# STM32G473CET6_PINOUT.net
KiCad netlist of a schematic drawn in Altium Designer
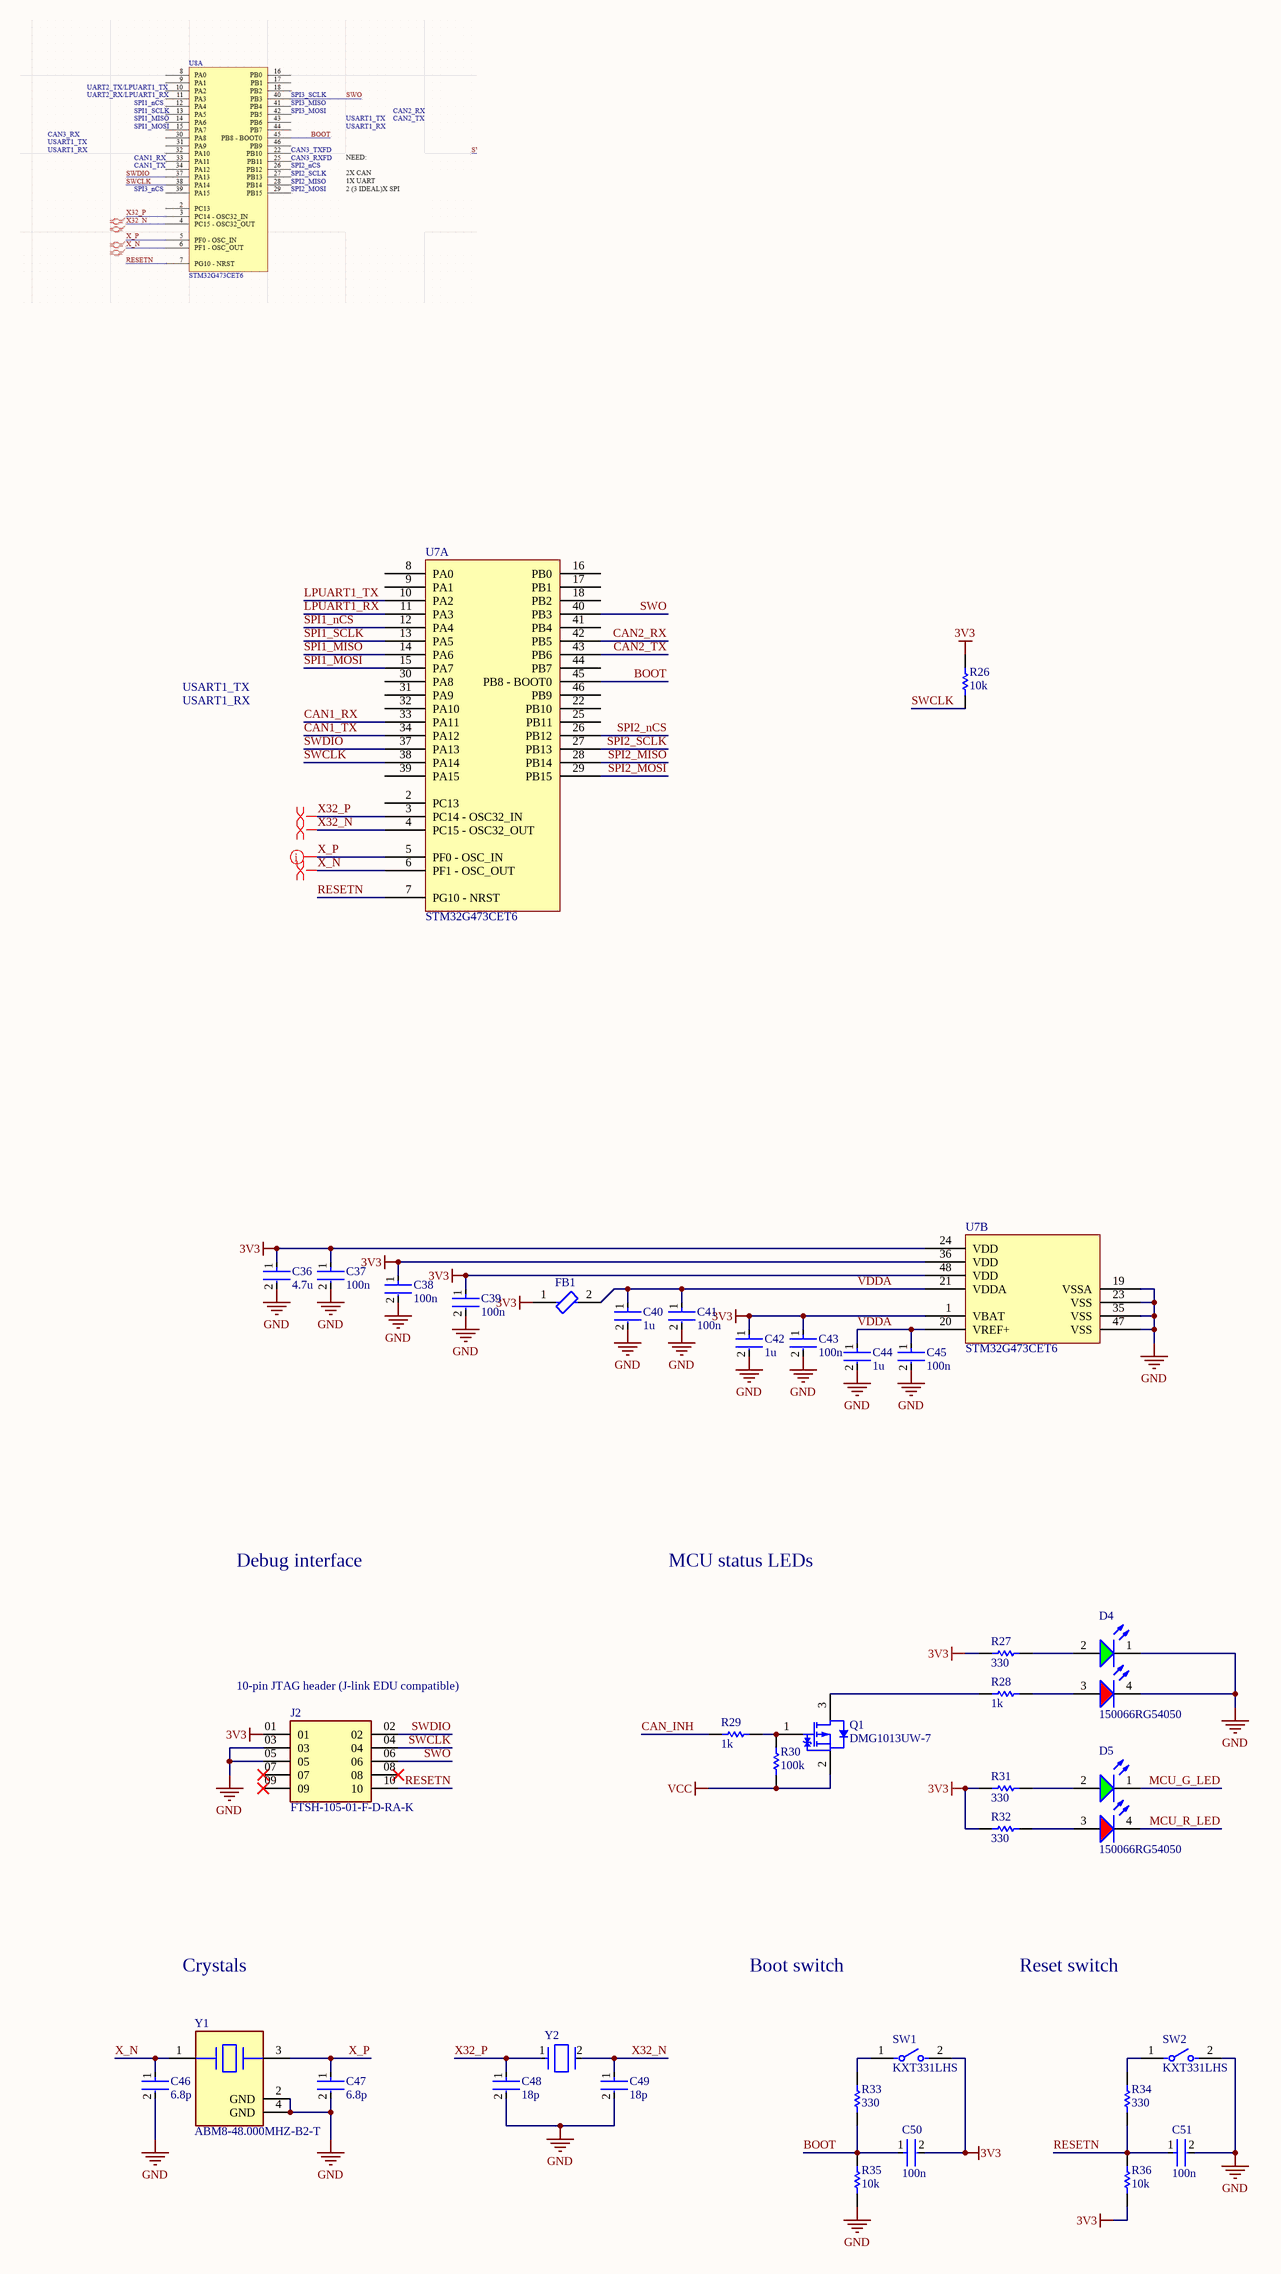
[diagram p0: STM32G473CET6_PINOUT.SchDoc]

(export (version "E")
  (design (tool "Eeschema 10.0.6"))
  (components
    (comp (ref "C36")
      (value "4.7u")
      (footprint "FP-0402-L_1_0_0_05-W_0_5-IPC_A")
      (description "LARGE PADS, 0402 CAP, CHANGE COMMENT TO MATCH REAL P/N")
      (libsource (lib "Space Concordia") (part "b4654b650e69147ec39a6b967a45e02"))
    )
    (comp (ref "C37")
      (value "100n")
      (footprint "FP-0402-L_1_0_0_05-W_0_5-IPC_A")
      (description "LARGE PADS, 0402 CAP, CHANGE COMMENT TO MATCH REAL P/N")
      (libsource (lib "Space Concordia") (part "b4654b650e69147ec39a6b967a45e02"))
    )
    (comp (ref "C38")
      (value "100n")
      (footprint "FP-0402-L_1_0_0_05-W_0_5-IPC_A")
      (description "LARGE PADS, 0402 CAP, CHANGE COMMENT TO MATCH REAL P/N")
      (libsource (lib "Space Concordia") (part "b4654b650e69147ec39a6b967a45e02"))
    )
    (comp (ref "C39")
      (value "100n")
      (footprint "FP-0402-L_1_0_0_05-W_0_5-IPC_A")
      (description "LARGE PADS, 0402 CAP, CHANGE COMMENT TO MATCH REAL P/N")
      (libsource (lib "Space Concordia") (part "b4654b650e69147ec39a6b967a45e02"))
    )
    (comp (ref "C40")
      (value "1u")
      (footprint "FP-0402-L_1_0_0_05-W_0_5-IPC_A")
      (description "LARGE PADS, 0402 CAP, CHANGE COMMENT TO MATCH REAL P/N")
      (libsource (lib "Space Concordia") (part "b4654b650e69147ec39a6b967a45e02"))
    )
    (comp (ref "C41")
      (value "100n")
      (footprint "FP-0402-L_1_0_0_05-W_0_5-IPC_A")
      (description "LARGE PADS, 0402 CAP, CHANGE COMMENT TO MATCH REAL P/N")
      (libsource (lib "Space Concordia") (part "b4654b650e69147ec39a6b967a45e02"))
    )
    (comp (ref "C42")
      (value "1u")
      (footprint "FP-0402-L_1_0_0_05-W_0_5-IPC_A")
      (description "LARGE PADS, 0402 CAP, CHANGE COMMENT TO MATCH REAL P/N")
      (libsource (lib "Space Concordia") (part "b4654b650e69147ec39a6b967a45e02"))
    )
    (comp (ref "C43")
      (value "100n")
      (footprint "FP-0402-L_1_0_0_05-W_0_5-IPC_A")
      (description "LARGE PADS, 0402 CAP, CHANGE COMMENT TO MATCH REAL P/N")
      (libsource (lib "Space Concordia") (part "b4654b650e69147ec39a6b967a45e02"))
    )
    (comp (ref "C44")
      (value "1u")
      (footprint "FP-0402-L_1_0_0_05-W_0_5-IPC_A")
      (description "LARGE PADS, 0402 CAP, CHANGE COMMENT TO MATCH REAL P/N")
      (libsource (lib "Space Concordia") (part "b4654b650e69147ec39a6b967a45e02"))
    )
    (comp (ref "C45")
      (value "100n")
      (footprint "FP-0402-L_1_0_0_05-W_0_5-IPC_A")
      (description "LARGE PADS, 0402 CAP, CHANGE COMMENT TO MATCH REAL P/N")
      (libsource (lib "Space Concordia") (part "b4654b650e69147ec39a6b967a45e02"))
    )
    (comp (ref "C46")
      (value "6.8p")
      (footprint "FP-0402-L_1_0_0_05-W_0_5-IPC_A")
      (description "LARGE PADS, 0402 CAP, CHANGE COMMENT TO MATCH REAL P/N")
      (libsource (lib "Space Concordia") (part "b4654b650e69147ec39a6b967a45e02"))
    )
    (comp (ref "C47")
      (value "6.8p")
      (footprint "FP-0402-L_1_0_0_05-W_0_5-IPC_A")
      (description "LARGE PADS, 0402 CAP, CHANGE COMMENT TO MATCH REAL P/N")
      (libsource (lib "Space Concordia") (part "b4654b650e69147ec39a6b967a45e02"))
    )
    (comp (ref "C48")
      (value "18p")
      (footprint "FP-0402-L_1_0_0_05-W_0_5-IPC_A")
      (description "LARGE PADS, 0402 CAP, CHANGE COMMENT TO MATCH REAL P/N")
      (libsource (lib "Space Concordia") (part "b4654b650e69147ec39a6b967a45e02"))
    )
    (comp (ref "C49")
      (value "18p")
      (footprint "FP-0402-L_1_0_0_05-W_0_5-IPC_A")
      (description "LARGE PADS, 0402 CAP, CHANGE COMMENT TO MATCH REAL P/N")
      (libsource (lib "Space Concordia") (part "b4654b650e69147ec39a6b967a45e02"))
    )
    (comp (ref "C50")
      (value "100n")
      (footprint "FP-0402-L_1_0_0_05-W_0_5-IPC_A")
      (description "LARGE PADS, 0402 CAP, CHANGE COMMENT TO MATCH REAL P/N")
      (libsource (lib "Space Concordia") (part "b4654b650e69147ec39a6b967a45e02"))
    )
    (comp (ref "C51")
      (value "100n")
      (footprint "FP-0402-L_1_0_0_05-W_0_5-IPC_A")
      (description "LARGE PADS, 0402 CAP, CHANGE COMMENT TO MATCH REAL P/N")
      (libsource (lib "Space Concordia") (part "b4654b650e69147ec39a6b967a45e02"))
    )
    (comp (ref "D4")
      (value "150066RG54050")
      (footprint "WL-SBCD_0606")
      (description "Led, Red/Grn, 180Mcd/230Mcd, 624Nm/525Nm Rohs Compliant: Yes")
      (fields (field (name "SOURCE") "rgled.SchLib"))
      (libsource (lib "Space Concordia") (part "CMP-004-00034-2"))
    )
    (comp (ref "D5")
      (value "150066RG54050")
      (footprint "WL-SBCD_0606")
      (description "Led, Red/Grn, 180Mcd/230Mcd, 624Nm/525Nm Rohs Compliant: Yes")
      (fields (field (name "SOURCE") "rgled.SchLib"))
      (libsource (lib "Space Concordia") (part "CMP-004-00034-2"))
    )
    (comp (ref "FB1")
      (value "BLM15PX601SN1D")
      (footprint "FP-BLM15-0_05-MFG")
      (description "Chip Ferrite Bead, 0402, 600Ω @ 100MHz, 0.23Ω, 25%, 900mA")
      (fields (field (name "TOLERANCE") "25%"))
      (libsource (lib "Altium Content Vault") (part "5f30dd21d616792df468990f7003faa"))
    )
    (comp (ref "J2")
      (value "FTSH-105-01-F-D-RA-K")
      (footprint "FTSH-105-01-F-D-RA-K-Footprint-1")
      (libsource (lib "Space Concordia") (part "FTSH-105-01-F-D-RA-K-Symbol-1"))
    )
    (comp (ref "Q1")
      (value "DMG1013UW-7")
      (footprint "DIOD-SOT323-3_V")
      (fields (field (name "MANUFACTURER") "Diodes Inc"))
      (libsource (lib "Altium Content Vault") (part "PEMOS-GSD-3_C"))
    )
    (comp (ref "R26")
      (value "10k")
      (footprint "R0603B")
      (description "Resistor")
      (libsource (lib "Space Concordia") (part "Resistor"))
    )
    (comp (ref "R27")
      (value "330")
      (footprint "R0603B")
      (description "Resistor")
      (libsource (lib "Space Concordia") (part "Resistor"))
    )
    (comp (ref "R28")
      (value "1k")
      (footprint "R0603B")
      (description "Resistor")
      (libsource (lib "Space Concordia") (part "Resistor"))
    )
    (comp (ref "R29")
      (value "1k")
      (footprint "R0603B")
      (description "Resistor")
      (libsource (lib "Space Concordia") (part "Resistor"))
    )
    (comp (ref "R30")
      (value "100k")
      (footprint "R0603B")
      (description "Resistor")
      (libsource (lib "Space Concordia") (part "Resistor"))
    )
    (comp (ref "R31")
      (value "330")
      (footprint "R0603B")
      (description "Resistor")
      (libsource (lib "Space Concordia") (part "Resistor"))
    )
    (comp (ref "R32")
      (value "330")
      (footprint "R0603B")
      (description "Resistor")
      (libsource (lib "Space Concordia") (part "Resistor"))
    )
    (comp (ref "R33")
      (value "330")
      (footprint "R0603B")
      (description "Resistor")
      (libsource (lib "Space Concordia") (part "Resistor"))
    )
    (comp (ref "R34")
      (value "330")
      (footprint "R0603B")
      (description "Resistor")
      (libsource (lib "Space Concordia") (part "Resistor"))
    )
    (comp (ref "R35")
      (value "10k")
      (footprint "R0603B")
      (description "Resistor")
      (libsource (lib "Space Concordia") (part "Resistor"))
    )
    (comp (ref "R36")
      (value "10k")
      (footprint "R0603B")
      (description "Resistor")
      (libsource (lib "Space Concordia") (part "Resistor"))
    )
    (comp (ref "SW1")
      (value "KXT331LHS")
      (footprint "FP-KXT331LHS-MFG")
      (description "SWITCH TACTILE SPST-NO 0.02A 15V")
      (libsource (lib "Altium Content Vault") (part "bb27bde45df87f1f469753f287ef5ae"))
    )
    (comp (ref "SW2")
      (value "KXT331LHS")
      (footprint "FP-KXT331LHS-MFG")
      (description "SWITCH TACTILE SPST-NO 0.02A 15V")
      (libsource (lib "Altium Content Vault") (part "bb27bde45df87f1f469753f287ef5ae"))
    )
    (comp (ref "U7")
      (value "STM32G473CET6")
      (footprint "TSQFP50P900X900X160-48N")
      (description "RISC Microcontroller, 32-Bit, 170MHz")
      (libsource (lib "Space Concordia") (part "STM32G473CET6"))
    )
    (comp (ref "Y1")
      (value "ABM8-48.000MHZ-B2-T")
      (footprint "FP-ABM8-MFG")
      (description "Crystal 48MHz ±20ppm 18pF SMD-4 3.2mm x 2.5mm")
      (fields (field (name "TOLERANCE") "20ppm"))
      (libsource (lib "Altium Content Vault") (part "dfdb7f9a12507849fb681da9a70121c"))
    )
    (comp (ref "Y2")
      (value "ECS-.327-12.5-1210-TR")
      (footprint "FP-ECX-1210-MFG")
      (description "CRYSTAL 32.7680KHZ 12.5PF SMD")
      (fields
        (field (name "OCTOPART") "https://octopart.com/ecs-.327-12.5-1210-tr-ecs+international-81221340")
        (field (name "TOLERANCE") "20ppm")
      )
      (libsource (lib "Altium Content Vault") (part "99724985039315a44fd0d1401b84e49"))
    )
  )
  (nets
    (net (code "1") (name "/BOOT") (class "Default")
      (node (ref "C50") (pin "1") (pinfunction "1_1") (pintype "passive"))
      (node (ref "R33") (pin "1") (pinfunction "1_1") (pintype "passive"))
      (node (ref "R35") (pin "2") (pinfunction "2_2") (pintype "passive"))
      (node (ref "U7") (pin "45") (pinfunction "PB8_-_BOOT0_45") (pintype "passive"))
    )
    (net (code "2") (name "/CAN1_RX") (class "Default")
      (node (ref "U7") (pin "33") (pinfunction "PA11_33") (pintype "passive"))
    )
    (net (code "3") (name "/CAN1_TX") (class "Default")
      (node (ref "U7") (pin "34") (pinfunction "PA12_34") (pintype "passive"))
    )
    (net (code "4") (name "/CAN2_RX") (class "Default")
      (node (ref "U7") (pin "42") (pinfunction "PB5_42") (pintype "passive"))
    )
    (net (code "5") (name "/CAN2_TX") (class "Default")
      (node (ref "U7") (pin "43") (pinfunction "PB6_43") (pintype "passive"))
    )
    (net (code "6") (name "/CAN_INH") (class "Default")
      (node (ref "R29") (pin "2") (pinfunction "2_2") (pintype "passive"))
    )
    (net (code "7") (name "/LPUART1_RX") (class "Default")
      (node (ref "U7") (pin "11") (pinfunction "PA3_11") (pintype "passive"))
    )
    (net (code "8") (name "/LPUART1_TX") (class "Default")
      (node (ref "U7") (pin "10") (pinfunction "PA2_10") (pintype "passive"))
    )
    (net (code "9") (name "/MCU_G_LED") (class "Default")
      (node (ref "D5") (pin "1") (pinfunction "K_1") (pintype "passive"))
    )
    (net (code "10") (name "/MCU_R_LED") (class "Default")
      (node (ref "D5") (pin "4") (pinfunction "K_4") (pintype "passive"))
    )
    (net (code "11") (name "/RESETN") (class "Default")
      (node (ref "C51") (pin "1") (pinfunction "1_1") (pintype "passive"))
      (node (ref "J2") (pin "10") (pinfunction "10_10") (pintype "passive"))
      (node (ref "R34") (pin "1") (pinfunction "1_1") (pintype "passive"))
      (node (ref "R36") (pin "2") (pinfunction "2_2") (pintype "passive"))
      (node (ref "U7") (pin "7") (pinfunction "PG10_-_NRST_7") (pintype "passive"))
    )
    (net (code "12") (name "/SPI1_MISO") (class "Default")
      (node (ref "U7") (pin "14") (pinfunction "PA6_14") (pintype "passive"))
    )
    (net (code "13") (name "/SPI1_MOSI") (class "Default")
      (node (ref "U7") (pin "15") (pinfunction "PA7_15") (pintype "passive"))
    )
    (net (code "14") (name "/SPI1_SCLK") (class "Default")
      (node (ref "U7") (pin "13") (pinfunction "PA5_13") (pintype "passive"))
    )
    (net (code "15") (name "/SPI1_nCS") (class "Default")
      (node (ref "U7") (pin "12") (pinfunction "PA4_12") (pintype "passive"))
    )
    (net (code "16") (name "/SPI2_MISO") (class "Default")
      (node (ref "U7") (pin "28") (pinfunction "PB14_28") (pintype "passive"))
    )
    (net (code "17") (name "/SPI2_MOSI") (class "Default")
      (node (ref "U7") (pin "29") (pinfunction "PB15_29") (pintype "passive"))
    )
    (net (code "18") (name "/SPI2_SCLK") (class "Default")
      (node (ref "U7") (pin "27") (pinfunction "PB13_27") (pintype "passive"))
    )
    (net (code "19") (name "/SPI2_nCS") (class "Default")
      (node (ref "U7") (pin "26") (pinfunction "PB12_26") (pintype "passive"))
    )
    (net (code "20") (name "/SWCLK") (class "Default")
      (node (ref "J2") (pin "04") (pinfunction "04_04") (pintype "passive"))
      (node (ref "R26") (pin "1") (pinfunction "1_1") (pintype "passive"))
      (node (ref "U7") (pin "38") (pinfunction "PA14_38") (pintype "passive"))
    )
    (net (code "21") (name "/SWDIO") (class "Default")
      (node (ref "J2") (pin "02") (pinfunction "02_02") (pintype "passive"))
      (node (ref "U7") (pin "37") (pinfunction "PA13_37") (pintype "passive"))
    )
    (net (code "22") (name "/SWO") (class "Default")
      (node (ref "J2") (pin "06") (pinfunction "06_06") (pintype "passive"))
      (node (ref "U7") (pin "40") (pinfunction "PB3_40") (pintype "passive"))
    )
    (net (code "23") (name "/VDDA") (class "Default")
      (node (ref "C40") (pin "1") (pinfunction "1_1") (pintype "passive"))
      (node (ref "C41") (pin "1") (pinfunction "1_1") (pintype "passive"))
      (node (ref "C44") (pin "1") (pinfunction "1_1") (pintype "passive"))
      (node (ref "C45") (pin "1") (pinfunction "1_1") (pintype "passive"))
      (node (ref "FB1") (pin "2") (pinfunction "2_2") (pintype "passive"))
      (node (ref "U7") (pin "20") (pinfunction "VREF+_20") (pintype "passive"))
      (node (ref "U7") (pin "21") (pinfunction "VDDA_21") (pintype "passive"))
    )
    (net (code "24") (name "/X32_N") (class "Default")
      (node (ref "C49") (pin "1") (pinfunction "1_1") (pintype "passive"))
      (node (ref "U7") (pin "4") (pinfunction "PC15_-_OSC32_OUT_4") (pintype "passive"))
      (node (ref "Y2") (pin "2") (pinfunction "Out/In_2") (pintype "passive"))
    )
    (net (code "25") (name "/X32_P") (class "Default")
      (node (ref "C48") (pin "1") (pinfunction "1_1") (pintype "passive"))
      (node (ref "U7") (pin "3") (pinfunction "PC14_-_OSC32_IN_3") (pintype "passive"))
      (node (ref "Y2") (pin "1") (pinfunction "In/Out_1") (pintype "passive"))
    )
    (net (code "26") (name "/X_N") (class "Default")
      (node (ref "C46") (pin "1") (pinfunction "1_1") (pintype "passive"))
      (node (ref "U7") (pin "6") (pinfunction "PF1_-_OSC_OUT_6") (pintype "passive"))
      (node (ref "Y1") (pin "1") (pinfunction "1_1") (pintype "passive"))
    )
    (net (code "27") (name "/X_P") (class "Default")
      (node (ref "C47") (pin "1") (pinfunction "1_1") (pintype "passive"))
      (node (ref "U7") (pin "5") (pinfunction "PF0_-_OSC_IN_5") (pintype "passive"))
      (node (ref "Y1") (pin "3") (pinfunction "3_3") (pintype "passive"))
    )
    (net (code "28") (name "3V3") (class "Default")
      (node (ref "C36") (pin "1") (pinfunction "1_1") (pintype "passive"))
      (node (ref "C37") (pin "1") (pinfunction "1_1") (pintype "passive"))
      (node (ref "C38") (pin "1") (pinfunction "1_1") (pintype "passive"))
      (node (ref "C39") (pin "1") (pinfunction "1_1") (pintype "passive"))
      (node (ref "C42") (pin "1") (pinfunction "1_1") (pintype "passive"))
      (node (ref "C43") (pin "1") (pinfunction "1_1") (pintype "passive"))
      (node (ref "C50") (pin "2") (pinfunction "2_2") (pintype "passive"))
      (node (ref "FB1") (pin "1") (pinfunction "1_1") (pintype "passive"))
      (node (ref "J2") (pin "01") (pinfunction "01_01") (pintype "passive"))
      (node (ref "R26") (pin "2") (pinfunction "2_2") (pintype "passive"))
      (node (ref "R27") (pin "2") (pinfunction "2_2") (pintype "passive"))
      (node (ref "R31") (pin "2") (pinfunction "2_2") (pintype "passive"))
      (node (ref "R32") (pin "2") (pinfunction "2_2") (pintype "passive"))
      (node (ref "R36") (pin "1") (pinfunction "1_1") (pintype "passive"))
      (node (ref "SW1") (pin "2") (pinfunction "2_2") (pintype "passive"))
      (node (ref "U7") (pin "1") (pinfunction "VBAT_1") (pintype "passive"))
      (node (ref "U7") (pin "24") (pinfunction "VDD_24") (pintype "passive"))
      (node (ref "U7") (pin "36") (pinfunction "VDD_36") (pintype "passive"))
      (node (ref "U7") (pin "48") (pinfunction "VDD_48") (pintype "passive"))
    )
    (net (code "29") (name "GND") (class "Default")
      (node (ref "C36") (pin "2") (pinfunction "2_2") (pintype "passive"))
      (node (ref "C37") (pin "2") (pinfunction "2_2") (pintype "passive"))
      (node (ref "C38") (pin "2") (pinfunction "2_2") (pintype "passive"))
      (node (ref "C39") (pin "2") (pinfunction "2_2") (pintype "passive"))
      (node (ref "C40") (pin "2") (pinfunction "2_2") (pintype "passive"))
      (node (ref "C41") (pin "2") (pinfunction "2_2") (pintype "passive"))
      (node (ref "C42") (pin "2") (pinfunction "2_2") (pintype "passive"))
      (node (ref "C43") (pin "2") (pinfunction "2_2") (pintype "passive"))
      (node (ref "C44") (pin "2") (pinfunction "2_2") (pintype "passive"))
      (node (ref "C45") (pin "2") (pinfunction "2_2") (pintype "passive"))
      (node (ref "C46") (pin "2") (pinfunction "2_2") (pintype "passive"))
      (node (ref "C47") (pin "2") (pinfunction "2_2") (pintype "passive"))
      (node (ref "C48") (pin "2") (pinfunction "2_2") (pintype "passive"))
      (node (ref "C49") (pin "2") (pinfunction "2_2") (pintype "passive"))
      (node (ref "C51") (pin "2") (pinfunction "2_2") (pintype "passive"))
      (node (ref "D4") (pin "1") (pinfunction "K_1") (pintype "passive"))
      (node (ref "D4") (pin "4") (pinfunction "K_4") (pintype "passive"))
      (node (ref "J2") (pin "03") (pinfunction "03_03") (pintype "passive"))
      (node (ref "J2") (pin "05") (pinfunction "05_05") (pintype "passive"))
      (node (ref "R35") (pin "1") (pinfunction "1_1") (pintype "passive"))
      (node (ref "SW2") (pin "2") (pinfunction "2_2") (pintype "passive"))
      (node (ref "U7") (pin "19") (pinfunction "VSSA_19") (pintype "passive"))
      (node (ref "U7") (pin "23") (pinfunction "VSS_23") (pintype "passive"))
      (node (ref "U7") (pin "35") (pinfunction "VSS_35") (pintype "passive"))
      (node (ref "U7") (pin "47") (pinfunction "VSS_47") (pintype "passive"))
      (node (ref "Y1") (pin "2") (pinfunction "GND_2") (pintype "power_in"))
      (node (ref "Y1") (pin "4") (pinfunction "GND_4") (pintype "power_in"))
    )
    (net (code "30") (name "Net-(D4-A-Pad2)") (class "Default")
      (node (ref "D4") (pin "2") (pinfunction "A_2") (pintype "passive"))
      (node (ref "R27") (pin "1") (pinfunction "1_1") (pintype "passive"))
    )
    (net (code "31") (name "Net-(D4-A-Pad3)") (class "Default")
      (node (ref "D4") (pin "3") (pinfunction "A_3") (pintype "passive"))
      (node (ref "R28") (pin "1") (pinfunction "1_1") (pintype "passive"))
    )
    (net (code "32") (name "Net-(D5-A-Pad2)") (class "Default")
      (node (ref "D5") (pin "2") (pinfunction "A_2") (pintype "passive"))
      (node (ref "R31") (pin "1") (pinfunction "1_1") (pintype "passive"))
    )
    (net (code "33") (name "Net-(D5-A-Pad3)") (class "Default")
      (node (ref "D5") (pin "3") (pinfunction "A_3") (pintype "passive"))
      (node (ref "R32") (pin "1") (pinfunction "1_1") (pintype "passive"))
    )
    (net (code "34") (name "Net-(Q1-D)") (class "Default")
      (node (ref "Q1") (pin "3") (pinfunction "D_3") (pintype "passive"))
      (node (ref "R28") (pin "2") (pinfunction "2_2") (pintype "passive"))
    )
    (net (code "35") (name "Net-(Q1-G)") (class "Default")
      (node (ref "Q1") (pin "1") (pinfunction "G_1") (pintype "passive"))
      (node (ref "R29") (pin "1") (pinfunction "1_1") (pintype "passive"))
      (node (ref "R30") (pin "1") (pinfunction "1_1") (pintype "passive"))
    )
    (net (code "36") (name "Net-(R33-Pad2)") (class "Default")
      (node (ref "R33") (pin "2") (pinfunction "2_2") (pintype "passive"))
      (node (ref "SW1") (pin "1") (pinfunction "1_1") (pintype "passive"))
    )
    (net (code "37") (name "Net-(R34-Pad2)") (class "Default")
      (node (ref "R34") (pin "2") (pinfunction "2_2") (pintype "passive"))
      (node (ref "SW2") (pin "1") (pinfunction "1_1") (pintype "passive"))
    )
    (net (code "38") (name "VCC") (class "Default")
      (node (ref "Q1") (pin "2") (pinfunction "S_2") (pintype "passive"))
      (node (ref "R30") (pin "2") (pinfunction "2_2") (pintype "passive"))
    )
    (net (code "39") (name "unconnected-(J2-Pad07)") (class "Default")
      (node (ref "J2") (pin "07") (pinfunction "07_07") (pintype "passive+no_connect"))
    )
    (net (code "40") (name "unconnected-(J2-Pad08)") (class "Default")
      (node (ref "J2") (pin "08") (pinfunction "08_08") (pintype "passive+no_connect"))
    )
    (net (code "41") (name "unconnected-(J2-Pad09)") (class "Default")
      (node (ref "J2") (pin "09") (pinfunction "09_09") (pintype "passive+no_connect"))
    )
    (net (code "42") (name "unconnected-(U7A-PA0-Pad8)") (class "Default")
      (node (ref "U7") (pin "8") (pinfunction "PA0_8") (pintype "passive"))
    )
    (net (code "43") (name "unconnected-(U7A-PA1-Pad9)") (class "Default")
      (node (ref "U7") (pin "9") (pinfunction "PA1_9") (pintype "passive"))
    )
    (net (code "44") (name "unconnected-(U7A-PA8-Pad30)") (class "Default")
      (node (ref "U7") (pin "30") (pinfunction "PA8_30") (pintype "passive"))
    )
    (net (code "45") (name "unconnected-(U7A-PA9-Pad31)") (class "Default")
      (node (ref "U7") (pin "31") (pinfunction "PA9_31") (pintype "passive"))
    )
    (net (code "46") (name "unconnected-(U7A-PA10-Pad32)") (class "Default")
      (node (ref "U7") (pin "32") (pinfunction "PA10_32") (pintype "passive"))
    )
    (net (code "47") (name "unconnected-(U7A-PA15-Pad39)") (class "Default")
      (node (ref "U7") (pin "39") (pinfunction "PA15_39") (pintype "passive"))
    )
    (net (code "48") (name "unconnected-(U7A-PB0-Pad16)") (class "Default")
      (node (ref "U7") (pin "16") (pinfunction "PB0_16") (pintype "passive"))
    )
    (net (code "49") (name "unconnected-(U7A-PB1-Pad17)") (class "Default")
      (node (ref "U7") (pin "17") (pinfunction "PB1_17") (pintype "passive"))
    )
    (net (code "50") (name "unconnected-(U7A-PB2-Pad18)") (class "Default")
      (node (ref "U7") (pin "18") (pinfunction "PB2_18") (pintype "passive"))
    )
    (net (code "51") (name "unconnected-(U7A-PB4-Pad41)") (class "Default")
      (node (ref "U7") (pin "41") (pinfunction "PB4_41") (pintype "passive"))
    )
    (net (code "52") (name "unconnected-(U7A-PB7-Pad44)") (class "Default")
      (node (ref "U7") (pin "44") (pinfunction "PB7_44") (pintype "passive"))
    )
    (net (code "53") (name "unconnected-(U7A-PB9-Pad46)") (class "Default")
      (node (ref "U7") (pin "46") (pinfunction "PB9_46") (pintype "passive"))
    )
    (net (code "54") (name "unconnected-(U7A-PB10-Pad22)") (class "Default")
      (node (ref "U7") (pin "22") (pinfunction "PB10_22") (pintype "passive"))
    )
    (net (code "55") (name "unconnected-(U7A-PB11-Pad25)") (class "Default")
      (node (ref "U7") (pin "25") (pinfunction "PB11_25") (pintype "passive"))
    )
    (net (code "56") (name "unconnected-(U7A-PC13-Pad2)") (class "Default")
      (node (ref "U7") (pin "2") (pinfunction "PC13_2") (pintype "passive"))
    )
  )
)
